# Microcontroller.net
KiCad netlist of a schematic drawn in Altium Designer
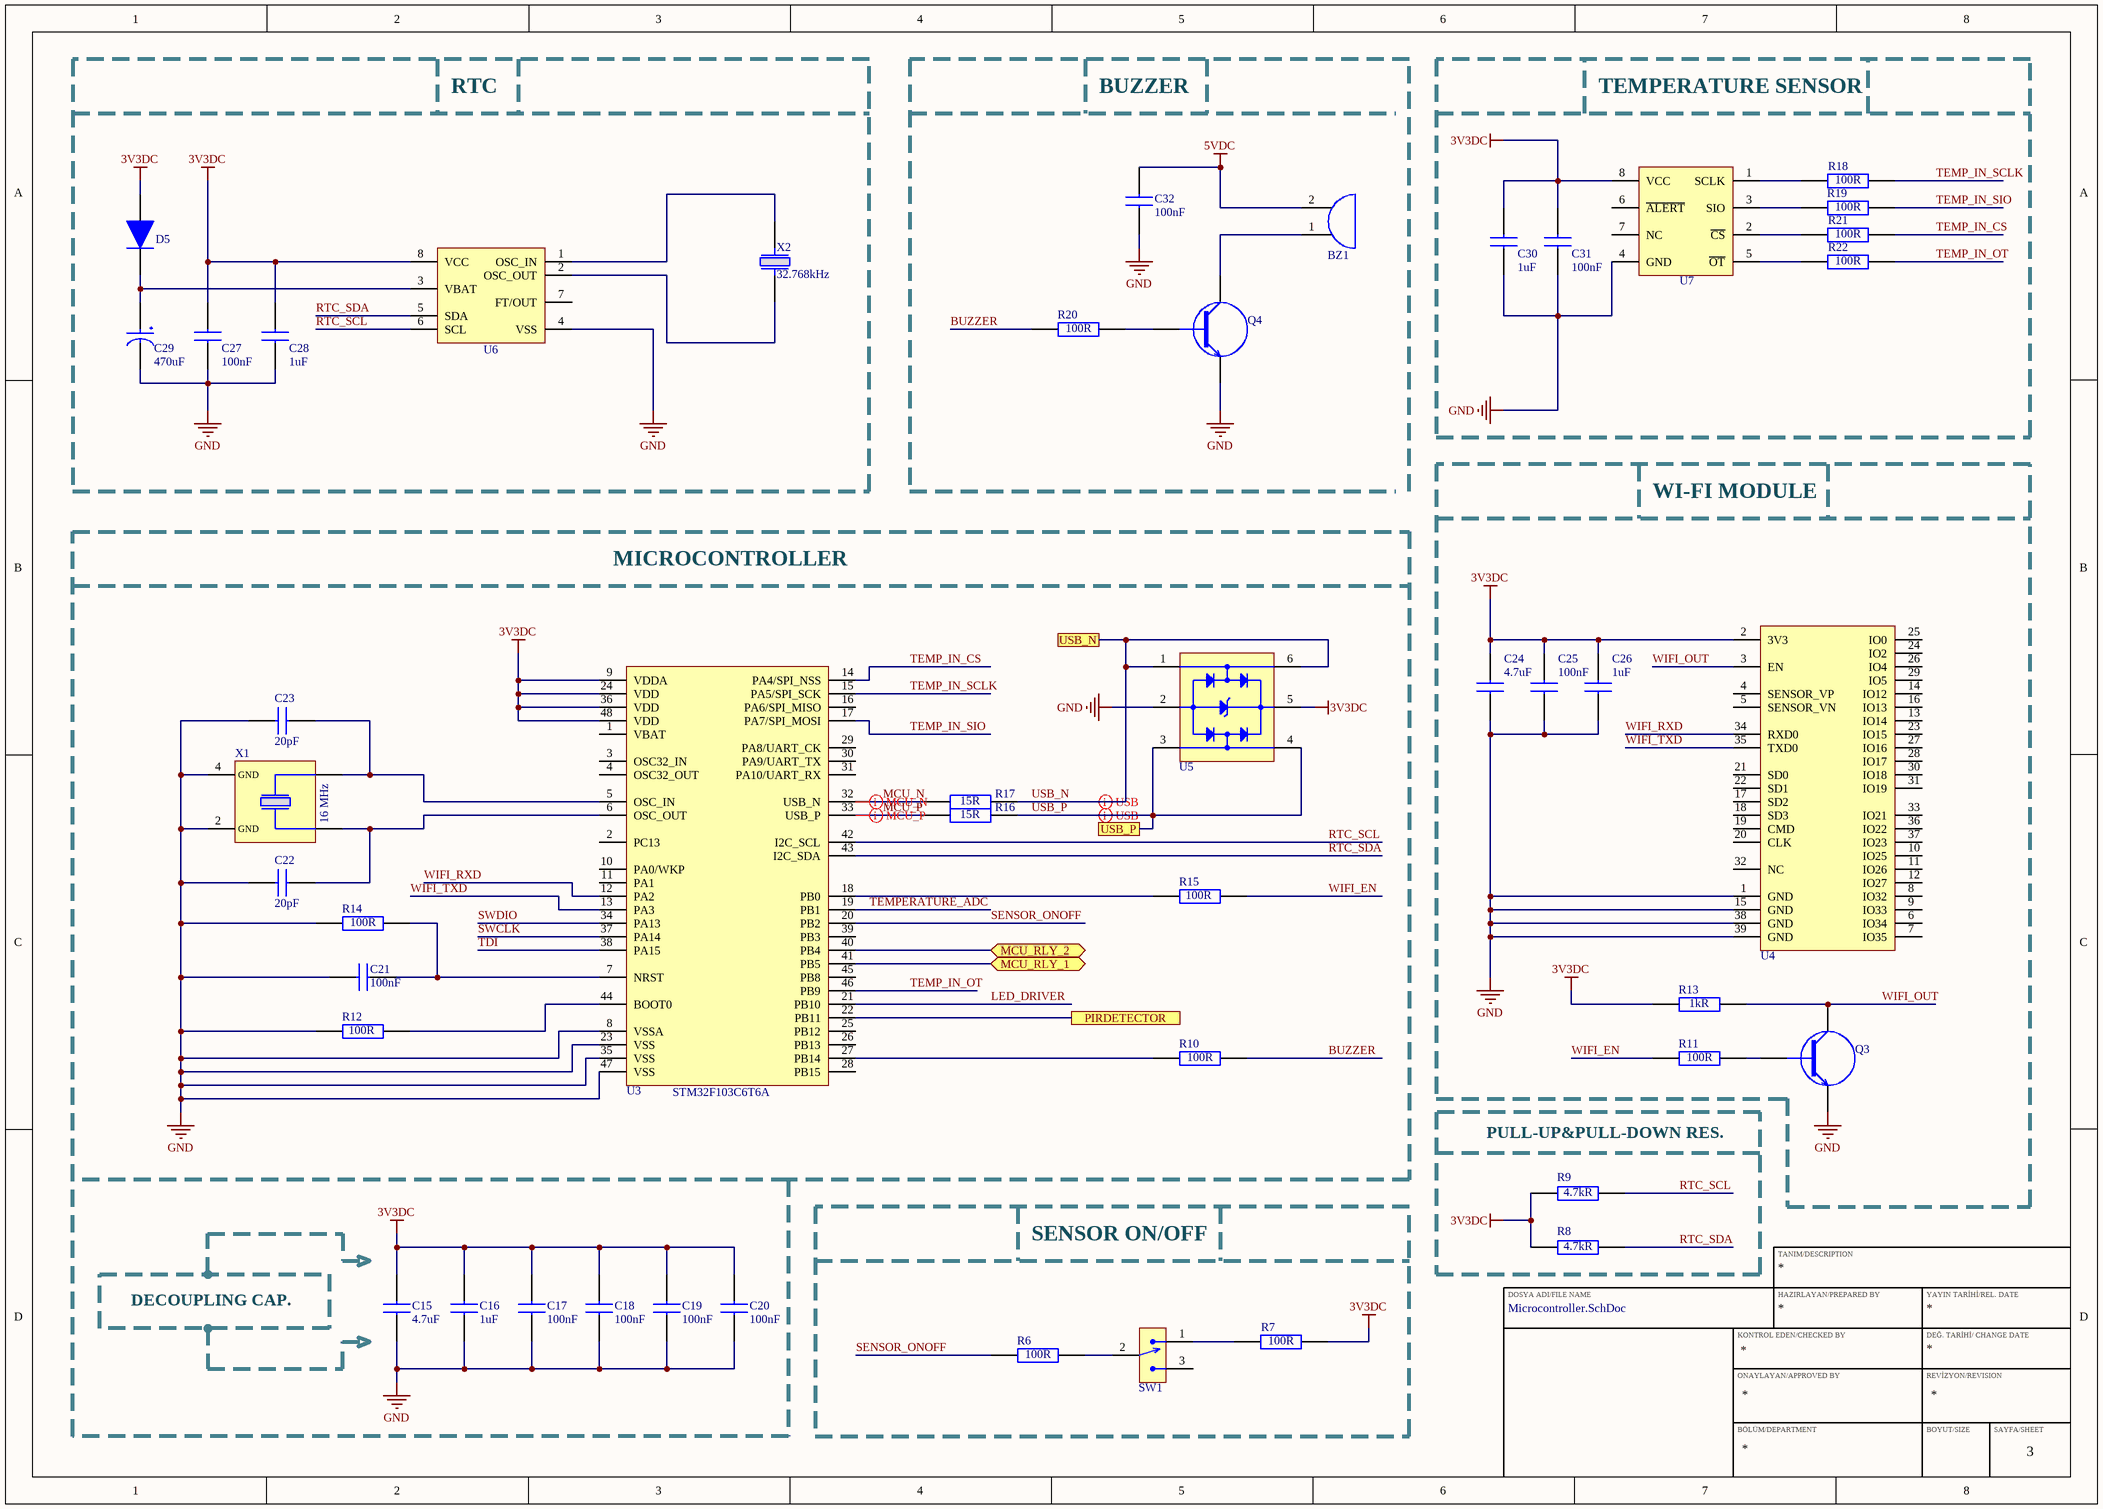
[diagram p0: Microcontroller.SchDoc]

(export (version "E")
  (design (tool "Eeschema 10.0.6"))
  (components
    (comp (ref "BZ1")
      (value "CMI-9605-0580T")
      (footprint "CMI-9605")
      (fields (field (name "MANUFACTURER") "CUI Devices") (field (name "DESIGNED BY") "ADAK"))
      (libsource (lib "Udemy_ADAK_Library1") (part "CMI-9605-0580T"))
    )
    (comp (ref "C15")
      (value "CL21A475KAQNNNE")
      (footprint "CAP_0805")
      (description "¦CAP CER 4.7UF %10 0805 SMD X5R")
      (fields
        (field (name "MANUFACTURER") "Samsung")
        (field (name "TOLERANCE") "10%")
        (field (name "CAPACITANCE") "4.7uF")
        (field (name "DESIGNED BY") "ADAK")
      )
      (libsource (lib "Udemy_ADAK_Library1") (part "CAP CER 4.7uF 0805"))
    )
    (comp (ref "C16")
      (value "CL21B105KBFNNNE")
      (footprint "CAP_0805")
      (description "¦CAP CER 1UF %10 0805 SMD X7R")
      (fields
        (field (name "MANUFACTURER") "Samsung")
        (field (name "TOLERANCE") "10%")
        (field (name "CAPACITANCE") "1uF")
        (field (name "DESIGNED BY") "ADAK")
      )
      (libsource (lib "Udemy_ADAK_Library1") (part "CAP CER 1uF 0805"))
    )
    (comp (ref "C17")
      (value "C0603C104K4RAC7867")
      (footprint "CAP_0603")
      (description "¦CAP CER 100nF (0.1UF) %10 0603 SMD")
      (fields
        (field (name "MANUFACTURER") "KEMET")
        (field (name "MANUFACTURER PART NUMBER") "C0603C104K4RACTU")
        (field (name "CAPACITANCE") "100nF")
        (field (name "DESIGNED BY") "ADAK")
      )
      (libsource (lib "Udemy_ADAK_Library1") (part "CAP CER 100nF 0603"))
    )
    (comp (ref "C18")
      (value "C0603C104K4RAC7867")
      (footprint "CAP_0603")
      (description "¦CAP CER 100nF (0.1UF) %10 0603 SMD")
      (fields
        (field (name "MANUFACTURER") "KEMET")
        (field (name "MANUFACTURER PART NUMBER") "C0603C104K4RACTU")
        (field (name "CAPACITANCE") "100nF")
        (field (name "DESIGNED BY") "ADAK")
      )
      (libsource (lib "Udemy_ADAK_Library1") (part "CAP CER 100nF 0603"))
    )
    (comp (ref "C19")
      (value "C0603C104K4RAC7867")
      (footprint "CAP_0603")
      (description "¦CAP CER 100nF (0.1UF) %10 0603 SMD")
      (fields
        (field (name "MANUFACTURER") "KEMET")
        (field (name "MANUFACTURER PART NUMBER") "C0603C104K4RACTU")
        (field (name "CAPACITANCE") "100nF")
        (field (name "DESIGNED BY") "ADAK")
      )
      (libsource (lib "Udemy_ADAK_Library1") (part "CAP CER 100nF 0603"))
    )
    (comp (ref "C20")
      (value "C0603C104K4RAC7867")
      (footprint "CAP_0603")
      (description "¦CAP CER 100nF (0.1UF) %10 0603 SMD")
      (fields
        (field (name "MANUFACTURER") "KEMET")
        (field (name "MANUFACTURER PART NUMBER") "C0603C104K4RACTU")
        (field (name "CAPACITANCE") "100nF")
        (field (name "DESIGNED BY") "ADAK")
      )
      (libsource (lib "Udemy_ADAK_Library1") (part "CAP CER 100nF 0603"))
    )
    (comp (ref "C21")
      (value "C0603C104K4RAC7867")
      (footprint "CAP_0603")
      (description "¦CAP CER 100nF (0.1UF) %10 0603 SMD")
      (fields
        (field (name "MANUFACTURER") "KEMET")
        (field (name "MANUFACTURER PART NUMBER") "C0603C104K4RACTU")
        (field (name "CAPACITANCE") "100nF")
        (field (name "DESIGNED BY") "ADAK")
      )
      (libsource (lib "Udemy_ADAK_Library1") (part "CAP CER 100nF 0603"))
    )
    (comp (ref "C22")
      (value "CL10C200JB8NNNC")
      (footprint "CAP_0603")
      (description "¦CAP CER 20pF %5 0603 SMD 50V")
      (fields
        (field (name "MANUFACTURER") "Samsung")
        (field (name "TOLERANCE") "5%")
        (field (name "CAPACITANCE") "20pF")
        (field (name "DESIGNED BY") "ADAK")
      )
      (libsource (lib "Udemy_ADAK_Library1") (part "CAP CER 20pF 0603"))
    )
    (comp (ref "C23")
      (value "CL10C200JB8NNNC")
      (footprint "CAP_0603")
      (description "¦CAP CER 20pF %5 0603 SMD 50V")
      (fields
        (field (name "MANUFACTURER") "Samsung")
        (field (name "TOLERANCE") "5%")
        (field (name "CAPACITANCE") "20pF")
        (field (name "DESIGNED BY") "ADAK")
      )
      (libsource (lib "Udemy_ADAK_Library1") (part "CAP CER 20pF 0603"))
    )
    (comp (ref "C24")
      (value "CL21A475KAQNNNE")
      (footprint "CAP_0805")
      (description "¦CAP CER 4.7UF %10 0805 SMD X5R")
      (fields
        (field (name "MANUFACTURER") "Samsung")
        (field (name "TOLERANCE") "10%")
        (field (name "CAPACITANCE") "4.7uF")
        (field (name "DESIGNED BY") "ADAK")
      )
      (libsource (lib "Udemy_ADAK_Library1") (part "CAP CER 4.7uF 0805"))
    )
    (comp (ref "C25")
      (value "CL21B104KBCNNNC")
      (footprint "CAP_0805")
      (description "¦CAP CER 0.1UF (100nF) %10 0805 SMD X7R")
      (fields
        (field (name "MANUFACTURER") "Samsung")
        (field (name "TOLERANCE") "10%")
        (field (name "CAPACITANCE") "100nF")
        (field (name "DESIGNED BY") "ADAK")
      )
      (libsource (lib "Udemy_ADAK_Library1") (part "CAP CER 100nF 0805"))
    )
    (comp (ref "C26")
      (value "CL21B105KBFNNNE")
      (footprint "CAP_0805")
      (description "¦CAP CER 1UF %10 0805 SMD X7R")
      (fields
        (field (name "MANUFACTURER") "Samsung")
        (field (name "TOLERANCE") "10%")
        (field (name "CAPACITANCE") "1uF")
        (field (name "DESIGNED BY") "ADAK")
      )
      (libsource (lib "Udemy_ADAK_Library1") (part "CAP CER 1uF 0805"))
    )
    (comp (ref "C27")
      (value "CL21B104KBCNNNC")
      (footprint "CAP_0805")
      (description "¦CAP CER 0.1UF (100nF) %10 0805 SMD X7R")
      (fields
        (field (name "MANUFACTURER") "Samsung")
        (field (name "TOLERANCE") "10%")
        (field (name "CAPACITANCE") "100nF")
        (field (name "DESIGNED BY") "ADAK")
      )
      (libsource (lib "Udemy_ADAK_Library1") (part "CAP CER 100nF 0805"))
    )
    (comp (ref "C28")
      (value "CL21B105KBFNNNE")
      (footprint "CAP_0805")
      (description "¦CAP CER 1UF %10 0805 SMD X7R")
      (fields
        (field (name "MANUFACTURER") "Samsung")
        (field (name "TOLERANCE") "10%")
        (field (name "CAPACITANCE") "1uF")
        (field (name "DESIGNED BY") "ADAK")
      )
      (libsource (lib "Udemy_ADAK_Library1") (part "CAP CER 1uF 0805"))
    )
    (comp (ref "C29")
      (value "ESH477M050AH4AA")
      (footprint "CAP_RADIAL_D10_P5")
      (description "¦CAP (AL) 470UF 20% 50V RADIAL")
      (fields
        (field (name "MANUFACTURER") "KEMET")
        (field (name "TOLERANCE") "20%")
        (field (name "CAPACITANCE") "470uF")
        (field (name "DESIGNED BY") "ADAK")
      )
      (libsource (lib "Udemy_ADAK_Library1") (part "CAP ALU ELEC 470uF 50V"))
    )
    (comp (ref "C30")
      (value "CL21B105KBFNNNE")
      (footprint "CAP_0805")
      (description "¦CAP CER 1UF %10 0805 SMD X7R")
      (fields
        (field (name "MANUFACTURER") "Samsung")
        (field (name "TOLERANCE") "10%")
        (field (name "CAPACITANCE") "1uF")
        (field (name "DESIGNED BY") "ADAK")
      )
      (libsource (lib "Udemy_ADAK_Library1") (part "CAP CER 1uF 0805"))
    )
    (comp (ref "C31")
      (value "CL21B104KBCNNNC")
      (footprint "CAP_0805")
      (description "¦CAP CER 0.1UF (100nF) %10 0805 SMD X7R")
      (fields
        (field (name "MANUFACTURER") "Samsung")
        (field (name "TOLERANCE") "10%")
        (field (name "CAPACITANCE") "100nF")
        (field (name "DESIGNED BY") "ADAK")
      )
      (libsource (lib "Udemy_ADAK_Library1") (part "CAP CER 100nF 0805"))
    )
    (comp (ref "C32")
      (value "CL21B104KBCNNNC")
      (footprint "CAP_0805")
      (description "¦CAP CER 0.1UF (100nF) %10 0805 SMD X7R")
      (fields
        (field (name "MANUFACTURER") "Samsung")
        (field (name "TOLERANCE") "10%")
        (field (name "CAPACITANCE") "100nF")
        (field (name "DESIGNED BY") "ADAK")
      )
      (libsource (lib "Udemy_ADAK_Library1") (part "CAP CER 100nF 0805"))
    )
    (comp (ref "D5")
      (value "1N4148WS")
      (footprint "SOD323F")
      (description "¦Diode 75 V 150mA Surface Mount SOD-323F")
      (fields
        (field (name "MANUFACTURER") "ON Semiconductor / Fairchild")
        (field (name "DESIGNED BY") "ADAK")
      )
      (libsource (lib "Udemy_ADAK_Library1") (part "1N4148WS"))
    )
    (comp (ref "Q3")
      (value "MMBT3904-7-F")
      (footprint "SOT-23F")
      (description "¦Bipolar (BJT) Transistor NPN 40 V 200 mA 300MHz 300 mW Surface Mount SOT-23-3")
      (fields (field (name "MANUFACTURER") "Diodes Zetex") (field (name "DESIGNED BY") "ADAK"))
      (libsource (lib "Udemy_ADAK_Library1") (part "MMBT3904-7-F"))
    )
    (comp (ref "Q4")
      (value "MMBT3904-7-F")
      (footprint "SOT-23F")
      (description "¦Bipolar (BJT) Transistor NPN 40 V 200 mA 300MHz 300 mW Surface Mount SOT-23-3")
      (fields (field (name "MANUFACTURER") "Diodes Zetex") (field (name "DESIGNED BY") "ADAK"))
      (libsource (lib "Udemy_ADAK_Library1") (part "MMBT3904-7-F"))
    )
    (comp (ref "R6")
      (value "RC0603JR-13100RL")
      (footprint "RES_0603")
      (description "¦RES 100Ω 5% 0603 SMD")
      (fields
        (field (name "MANUFACTURER") "Yageo")
        (field (name "TOLERANCE") "5%")
        (field (name "RESISTANCE") "100R")
        (field (name "DESIGNED BY") "ADAK")
      )
      (libsource (lib "Udemy_ADAK_Library1") (part "RES 100 OHM 0603"))
    )
    (comp (ref "R7")
      (value "RC0603JR-13100RL")
      (footprint "RES_0603")
      (description "¦RES 100Ω 5% 0603 SMD")
      (fields
        (field (name "MANUFACTURER") "Yageo")
        (field (name "TOLERANCE") "5%")
        (field (name "RESISTANCE") "100R")
        (field (name "DESIGNED BY") "ADAK")
      )
      (libsource (lib "Udemy_ADAK_Library1") (part "RES 100 OHM 0603"))
    )
    (comp (ref "R8")
      (value "RC0603JR-074K7L")
      (footprint "RES_0603")
      (description "¦RES 4K7Ω 5% 0603 SMD")
      (fields
        (field (name "MANUFACTURER") "Yageo")
        (field (name "TOLERANCE") "5%")
        (field (name "RESISTANCE") "4.7kR")
        (field (name "DESIGNED BY") "ADAK")
      )
      (libsource (lib "Udemy_ADAK_Library1") (part "RES 4K7 OHM 0603"))
    )
    (comp (ref "R9")
      (value "RC0603JR-074K7L")
      (footprint "RES_0603")
      (description "¦RES 4K7Ω 5% 0603 SMD")
      (fields
        (field (name "MANUFACTURER") "Yageo")
        (field (name "TOLERANCE") "5%")
        (field (name "RESISTANCE") "4.7kR")
        (field (name "DESIGNED BY") "ADAK")
      )
      (libsource (lib "Udemy_ADAK_Library1") (part "RES 4K7 OHM 0603"))
    )
    (comp (ref "R10")
      (value "RC0603JR-13100RL")
      (footprint "RES_0603")
      (description "¦RES 100Ω 5% 0603 SMD")
      (fields
        (field (name "MANUFACTURER") "Yageo")
        (field (name "TOLERANCE") "5%")
        (field (name "RESISTANCE") "100R")
        (field (name "DESIGNED BY") "ADAK")
      )
      (libsource (lib "Udemy_ADAK_Library1") (part "RES 100 OHM 0603"))
    )
    (comp (ref "R11")
      (value "RC0603JR-13100RL")
      (footprint "RES_0603")
      (description "¦RES 100Ω 5% 0603 SMD")
      (fields
        (field (name "MANUFACTURER") "Yageo")
        (field (name "TOLERANCE") "5%")
        (field (name "RESISTANCE") "100R")
        (field (name "DESIGNED BY") "ADAK")
      )
      (libsource (lib "Udemy_ADAK_Library1") (part "RES 100 OHM 0603"))
    )
    (comp (ref "R12")
      (value "RC0603JR-13100RL")
      (footprint "RES_0603")
      (description "¦RES 100Ω 5% 0603 SMD")
      (fields
        (field (name "MANUFACTURER") "Yageo")
        (field (name "TOLERANCE") "5%")
        (field (name "RESISTANCE") "100R")
        (field (name "DESIGNED BY") "ADAK")
      )
      (libsource (lib "Udemy_ADAK_Library1") (part "RES 100 OHM 0603"))
    )
    (comp (ref "R13")
      (value "RC0603FR-071KL")
      (footprint "RES_0603")
      (description "¦RES 1KΩ 1% 0603 SMD")
      (fields
        (field (name "MANUFACTURER") "Yageo")
        (field (name "TOLERANCE") "1%")
        (field (name "RESISTANCE") "1kR")
        (field (name "DESIGNED BY") "ADAK")
      )
      (libsource (lib "Udemy_ADAK_Library1") (part "RES 1K OHM 0603"))
    )
    (comp (ref "R14")
      (value "RC0603JR-13100RL")
      (footprint "RES_0603")
      (description "¦RES 100Ω 5% 0603 SMD")
      (fields
        (field (name "MANUFACTURER") "Yageo")
        (field (name "TOLERANCE") "5%")
        (field (name "RESISTANCE") "100R")
        (field (name "DESIGNED BY") "ADAK")
      )
      (libsource (lib "Udemy_ADAK_Library1") (part "RES 100 OHM 0603"))
    )
    (comp (ref "R15")
      (value "RC0603JR-13100RL")
      (footprint "RES_0603")
      (description "¦RES 100Ω 5% 0603 SMD")
      (fields
        (field (name "MANUFACTURER") "Yageo")
        (field (name "TOLERANCE") "5%")
        (field (name "RESISTANCE") "100R")
        (field (name "DESIGNED BY") "ADAK")
      )
      (libsource (lib "Udemy_ADAK_Library1") (part "RES 100 OHM 0603"))
    )
    (comp (ref "R16")
      (value "RC0603JR-0715RL")
      (footprint "RES_0603")
      (description "¦RES 15Ω 1% 0603 SMD")
      (fields
        (field (name "MANUFACTURER") "Yageo")
        (field (name "TOLERANCE") "5%")
        (field (name "RESISTANCE") "15R")
        (field (name "DESIGNED BY") "ADAK")
      )
      (libsource (lib "Udemy_ADAK_Library1") (part "RES 15 OHM 0603"))
    )
    (comp (ref "R17")
      (value "RC0603JR-0715RL")
      (footprint "RES_0603")
      (description "¦RES 15Ω 1% 0603 SMD")
      (fields
        (field (name "MANUFACTURER") "Yageo")
        (field (name "TOLERANCE") "5%")
        (field (name "RESISTANCE") "15R")
        (field (name "DESIGNED BY") "ADAK")
      )
      (libsource (lib "Udemy_ADAK_Library1") (part "RES 15 OHM 0603"))
    )
    (comp (ref "R18")
      (value "RC0603JR-13100RL")
      (footprint "RES_0603")
      (description "¦RES 100Ω 5% 0603 SMD")
      (fields
        (field (name "MANUFACTURER") "Yageo")
        (field (name "TOLERANCE") "5%")
        (field (name "RESISTANCE") "100R")
        (field (name "DESIGNED BY") "ADAK")
      )
      (libsource (lib "Udemy_ADAK_Library1") (part "RES 100 OHM 0603"))
    )
    (comp (ref "R19")
      (value "RC0603JR-13100RL")
      (footprint "RES_0603")
      (description "¦RES 100Ω 5% 0603 SMD")
      (fields
        (field (name "MANUFACTURER") "Yageo")
        (field (name "TOLERANCE") "5%")
        (field (name "RESISTANCE") "100R")
        (field (name "DESIGNED BY") "ADAK")
      )
      (libsource (lib "Udemy_ADAK_Library1") (part "RES 100 OHM 0603"))
    )
    (comp (ref "R20")
      (value "RC0603JR-13100RL")
      (footprint "RES_0603")
      (description "¦RES 100Ω 5% 0603 SMD")
      (fields
        (field (name "MANUFACTURER") "Yageo")
        (field (name "TOLERANCE") "5%")
        (field (name "RESISTANCE") "100R")
        (field (name "DESIGNED BY") "ADAK")
      )
      (libsource (lib "Udemy_ADAK_Library1") (part "RES 100 OHM 0603"))
    )
    (comp (ref "R21")
      (value "RC0603JR-13100RL")
      (footprint "RES_0603")
      (description "¦RES 100Ω 5% 0603 SMD")
      (fields
        (field (name "MANUFACTURER") "Yageo")
        (field (name "TOLERANCE") "5%")
        (field (name "RESISTANCE") "100R")
        (field (name "DESIGNED BY") "ADAK")
      )
      (libsource (lib "Udemy_ADAK_Library1") (part "RES 100 OHM 0603"))
    )
    (comp (ref "R22")
      (value "RC0603JR-13100RL")
      (footprint "RES_0603")
      (description "¦RES 100Ω 5% 0603 SMD")
      (fields
        (field (name "MANUFACTURER") "Yageo")
        (field (name "TOLERANCE") "5%")
        (field (name "RESISTANCE") "100R")
        (field (name "DESIGNED BY") "ADAK")
      )
      (libsource (lib "Udemy_ADAK_Library1") (part "RES 100 OHM 0603"))
    )
    (comp (ref "SW1")
      (value "EG1215AA")
      (footprint "EG1215AA")
      (description "¦Slide Switch SPDT Surface Mount, Right Angle")
      (fields
        (field (name "MANUFACTURER") "E-Switch")
        (field (name "TOLERANCE") "4.95%")
        (field (name "DESIGNED BY") "ADAK")
      )
      (libsource (lib "Udemy_ADAK_Library1") (part "EG1215AA"))
    )
    (comp (ref "U3")
      (value "STM32F103C6T6A")
      (footprint "LQFP-48")
      (description "¦MCU 32-bit STM32F ARM Cortex M3 RISC 32KB Flash 2.5V/3.3V 48-Pin LQFP Tray")
      (fields (field (name "MANUFACTURER") "STMicroelectronics") (field (name "DESIGNED BY") "ADAK"))
      (libsource (lib "Udemy_ADAK_Library1") (part "STM32F103C6T6A"))
    )
    (comp (ref "U4")
      (value "ESP32-WROOM-32E-N4")
      (footprint "ESP32-32E-N4")
      (fields
        (field (name "MANUFACTURER") "Espressif Systems")
        (field (name "MANUFACTURER PART NUMBER") "ESP32-WROOM-32E(M113EH3200PH3Q0)")
        (field (name "DESIGNED BY") "ADAK")
      )
      (libsource (lib "Udemy_ADAK_Library1") (part "ESP32-WROOM"))
    )
    (comp (ref "U5")
      (value "USBLC6-2SC6")
      (footprint "SOT23-6L")
      (description "¦17V Clamp 5A (8/20µs) Ipp Tvs Diode Surface Mount SOT-23-6")
      (fields (field (name "MANUFACTURER") "STMicroelectronics") (field (name "DESIGNED BY") "ADAK"))
      (libsource (lib "Udemy_ADAK_Library1") (part "USB PROTECTION"))
    )
    (comp (ref "U6")
      (value "M41T0M6F")
      (footprint "SOIC8")
      (description "¦RTC M41T0 Series 2 to 5.5 V Serial I2C Real Time Clock Surface Mount - SOIC-8")
      (fields (field (name "MANUFACTURER") "STMicroelectronics") (field (name "DESIGNED BY") "ADAK"))
      (libsource (lib "Udemy_ADAK_Library1") (part "M41T0M6F"))
    )
    (comp (ref "U7")
      (value "MAX6662MSA+")
      (footprint "SOIC8")
      (description "¦Temperature Sensor Digital, 8-SOIC, SPI")
      (fields (field (name "MANUFACTURER") "Maxim") (field (name "DESIGNED BY") "ADAK"))
      (libsource (lib "Udemy_ADAK_Library1") (part "MAX6662MSA+"))
    )
    (comp (ref "X1")
      (value "ECS-160-20-30B-TR")
      (footprint "ECS")
      (description "¦16 MHz ±30ppm Crystal 20pF 50 Ohms 4-SMD, No Lead")
      (fields
        (field (name "MANUFACTURER") "ECS International")
        (field (name "TOLERANCE") "50ppm")
        (field (name "FREQUENCY") "16 MHz")
        (field (name "DESIGNED BY") "ADAK")
      )
      (libsource (lib "Udemy_ADAK_Library1") (part "CRYSTAL 16MHZ"))
    )
    (comp (ref "X2")
      (value "ABS05-32.768KHZ-T")
      (footprint "ABS05")
      (description "¦32.768 kHz ±20ppm Crystal 12.5pF 90 kOhms 2-SMD, No Lead")
      (fields
        (field (name "MANUFACTURER") "Abracon")
        (field (name "TOLERANCE") "20ppm")
        (field (name "FREQUENCY") "32.768kHz")
        (field (name "DESIGNED BY") "ADAK")
      )
      (libsource (lib "Udemy_ADAK_Library1") (part "CRYSTAL 32.768kHZ"))
    )
  )
  (nets
    (net (code "1") (name "/BUZZER") (class "Default")
      (node (ref "R10") (pin "2") (pinfunction "2_2") (pintype "passive"))
      (node (ref "R20") (pin "1") (pinfunction "1_1") (pintype "passive"))
    )
    (net (code "2") (name "/LED_DRIVER") (class "Default")
      (node (ref "U3") (pin "21") (pinfunction "PB10_21") (pintype "passive"))
    )
    (net (code "3") (name "/MCU_N") (class "Default")
      (node (ref "R17") (pin "1") (pinfunction "1_1") (pintype "passive"))
      (node (ref "U3") (pin "32") (pinfunction "USB_N_32") (pintype "passive"))
    )
    (net (code "4") (name "/MCU_P") (class "Default")
      (node (ref "R16") (pin "1") (pinfunction "1_1") (pintype "passive"))
      (node (ref "U3") (pin "33") (pinfunction "USB_P_33") (pintype "passive"))
    )
    (net (code "5") (name "/MCU_RLY_1") (class "Default")
      (node (ref "U3") (pin "41") (pinfunction "PB5_41") (pintype "passive"))
    )
    (net (code "6") (name "/MCU_RLY_2") (class "Default")
      (node (ref "U3") (pin "40") (pinfunction "PB4_40") (pintype "passive"))
    )
    (net (code "7") (name "/PIRDETECTOR") (class "Default")
      (node (ref "U3") (pin "22") (pinfunction "PB11_22") (pintype "passive"))
    )
    (net (code "8") (name "/RTC_SCL") (class "Default")
      (node (ref "R9") (pin "1") (pinfunction "1_1") (pintype "passive"))
      (node (ref "U3") (pin "42") (pinfunction "I2C_SCL_42") (pintype "passive"))
      (node (ref "U6") (pin "6") (pinfunction "SCL_6") (pintype "passive"))
    )
    (net (code "9") (name "/RTC_SDA") (class "Default")
      (node (ref "R8") (pin "1") (pinfunction "1_1") (pintype "passive"))
      (node (ref "U3") (pin "43") (pinfunction "I2C_SDA_43") (pintype "passive"))
      (node (ref "U6") (pin "5") (pinfunction "SDA_5") (pintype "passive"))
    )
    (net (code "10") (name "/SENSOR_ONOFF") (class "Default")
      (node (ref "R6") (pin "1") (pinfunction "1_1") (pintype "passive"))
      (node (ref "U3") (pin "20") (pinfunction "PB2_20") (pintype "passive"))
    )
    (net (code "11") (name "/SWCLK") (class "Default")
      (node (ref "U3") (pin "37") (pinfunction "PA14_37") (pintype "passive"))
    )
    (net (code "12") (name "/SWDIO") (class "Default")
      (node (ref "U3") (pin "34") (pinfunction "PA13_34") (pintype "passive"))
    )
    (net (code "13") (name "/TDI") (class "Default")
      (node (ref "U3") (pin "38") (pinfunction "PA15_38") (pintype "passive"))
    )
    (net (code "14") (name "/TEMPERATURE_ADC") (class "Default")
      (node (ref "U3") (pin "19") (pinfunction "PB1_19") (pintype "passive"))
    )
    (net (code "15") (name "/TEMP_IN_CS") (class "Default")
      (node (ref "R21") (pin "1") (pinfunction "1_1") (pintype "passive"))
      (node (ref "U3") (pin "14") (pinfunction "PA4/SPI_NSS_14") (pintype "passive"))
    )
    (net (code "16") (name "/TEMP_IN_OT") (class "Default")
      (node (ref "R22") (pin "1") (pinfunction "1_1") (pintype "passive"))
      (node (ref "U3") (pin "46") (pinfunction "PB9_46") (pintype "passive"))
    )
    (net (code "17") (name "/TEMP_IN_SCLK") (class "Default")
      (node (ref "R18") (pin "1") (pinfunction "1_1") (pintype "passive"))
      (node (ref "U3") (pin "15") (pinfunction "PA5/SPI_SCK_15") (pintype "passive"))
    )
    (net (code "18") (name "/TEMP_IN_SIO") (class "Default")
      (node (ref "R19") (pin "1") (pinfunction "1_1") (pintype "passive"))
      (node (ref "U3") (pin "17") (pinfunction "PA7/SPI_MOSI_17") (pintype "passive"))
    )
    (net (code "19") (name "/USB_N") (class "Default")
      (node (ref "R17") (pin "2") (pinfunction "2_2") (pintype "passive"))
      (node (ref "U5") (pin "1") (pinfunction "I/O1_1") (pintype "passive"))
      (node (ref "U5") (pin "6") (pinfunction "I/O1_6") (pintype "passive"))
    )
    (net (code "20") (name "/USB_P") (class "Default")
      (node (ref "R16") (pin "2") (pinfunction "2_2") (pintype "passive"))
      (node (ref "U5") (pin "3") (pinfunction "I/O2_3") (pintype "passive"))
      (node (ref "U5") (pin "4") (pinfunction "I/O2_4") (pintype "passive"))
    )
    (net (code "21") (name "/WIFI_EN") (class "Default")
      (node (ref "R11") (pin "1") (pinfunction "1_1") (pintype "passive"))
      (node (ref "R15") (pin "2") (pinfunction "2_2") (pintype "passive"))
    )
    (net (code "22") (name "/WIFI_OUT") (class "Default")
      (node (ref "Q3") (pin "3") (pinfunction "C_3") (pintype "passive"))
      (node (ref "R13") (pin "2") (pinfunction "2_2") (pintype "passive"))
      (node (ref "U4") (pin "3") (pinfunction "EN_3") (pintype "passive"))
    )
    (net (code "23") (name "/WIFI_RXD") (class "Default")
      (node (ref "U3") (pin "12") (pinfunction "PA2_12") (pintype "passive"))
      (node (ref "U4") (pin "34") (pinfunction "RXD0_34") (pintype "passive"))
    )
    (net (code "24") (name "/WIFI_TXD") (class "Default")
      (node (ref "U3") (pin "13") (pinfunction "PA3_13") (pintype "passive"))
      (node (ref "U4") (pin "35") (pinfunction "TXD0_35") (pintype "passive"))
    )
    (net (code "25") (name "3V3DC") (class "Default")
      (node (ref "C15") (pin "2") (pinfunction "2_2") (pintype "passive"))
      (node (ref "C16") (pin "2") (pinfunction "2_2") (pintype "passive"))
      (node (ref "C17") (pin "2") (pinfunction "2_2") (pintype "passive"))
      (node (ref "C18") (pin "2") (pinfunction "2_2") (pintype "passive"))
      (node (ref "C19") (pin "2") (pinfunction "2_2") (pintype "passive"))
      (node (ref "C20") (pin "2") (pinfunction "2_2") (pintype "passive"))
      (node (ref "C24") (pin "2") (pinfunction "2_2") (pintype "passive"))
      (node (ref "C25") (pin "2") (pinfunction "2_2") (pintype "passive"))
      (node (ref "C26") (pin "2") (pinfunction "2_2") (pintype "passive"))
      (node (ref "C27") (pin "2") (pinfunction "2_2") (pintype "passive"))
      (node (ref "C28") (pin "2") (pinfunction "2_2") (pintype "passive"))
      (node (ref "C30") (pin "2") (pinfunction "2_2") (pintype "passive"))
      (node (ref "C31") (pin "2") (pinfunction "2_2") (pintype "passive"))
      (node (ref "D5") (pin "2") (pinfunction "2_2") (pintype "passive"))
      (node (ref "R13") (pin "1") (pinfunction "1_1") (pintype "passive"))
      (node (ref "R7") (pin "2") (pinfunction "2_2") (pintype "passive"))
      (node (ref "R8") (pin "2") (pinfunction "2_2") (pintype "passive"))
      (node (ref "R9") (pin "2") (pinfunction "2_2") (pintype "passive"))
      (node (ref "U3") (pin "24") (pinfunction "VDD_24") (pintype "passive"))
      (node (ref "U3") (pin "36") (pinfunction "VDD_36") (pintype "passive"))
      (node (ref "U3") (pin "48") (pinfunction "VDD_48") (pintype "passive"))
      (node (ref "U3") (pin "9") (pinfunction "VDDA_9") (pintype "passive"))
      (node (ref "U4") (pin "2") (pinfunction "3V3_2") (pintype "passive"))
      (node (ref "U5") (pin "5") (pinfunction "VBUS_5") (pintype "passive"))
      (node (ref "U6") (pin "8") (pinfunction "VCC_8") (pintype "passive"))
      (node (ref "U7") (pin "8") (pinfunction "VCC_8") (pintype "passive"))
    )
    (net (code "26") (name "5VDC") (class "Default")
      (node (ref "BZ1") (pin "2") (pinfunction "2_2") (pintype "passive"))
      (node (ref "C32") (pin "2") (pinfunction "2_2") (pintype "passive"))
    )
    (net (code "27") (name "GND") (class "Default")
      (node (ref "C15") (pin "1") (pinfunction "1_1") (pintype "passive"))
      (node (ref "C16") (pin "1") (pinfunction "1_1") (pintype "passive"))
      (node (ref "C17") (pin "1") (pinfunction "1_1") (pintype "passive"))
      (node (ref "C18") (pin "1") (pinfunction "1_1") (pintype "passive"))
      (node (ref "C19") (pin "1") (pinfunction "1_1") (pintype "passive"))
      (node (ref "C20") (pin "1") (pinfunction "1_1") (pintype "passive"))
      (node (ref "C21") (pin "1") (pinfunction "1_1") (pintype "passive"))
      (node (ref "C22") (pin "1") (pinfunction "1_1") (pintype "passive"))
      (node (ref "C23") (pin "1") (pinfunction "1_1") (pintype "passive"))
      (node (ref "C24") (pin "1") (pinfunction "1_1") (pintype "passive"))
      (node (ref "C25") (pin "1") (pinfunction "1_1") (pintype "passive"))
      (node (ref "C26") (pin "1") (pinfunction "1_1") (pintype "passive"))
      (node (ref "C27") (pin "1") (pinfunction "1_1") (pintype "passive"))
      (node (ref "C28") (pin "1") (pinfunction "1_1") (pintype "passive"))
      (node (ref "C29") (pin "2") (pinfunction "2_2") (pintype "passive"))
      (node (ref "C30") (pin "1") (pinfunction "1_1") (pintype "passive"))
      (node (ref "C31") (pin "1") (pinfunction "1_1") (pintype "passive"))
      (node (ref "C32") (pin "1") (pinfunction "1_1") (pintype "passive"))
      (node (ref "Q3") (pin "2") (pinfunction "E_2") (pintype "passive"))
      (node (ref "Q4") (pin "2") (pinfunction "E_2") (pintype "passive"))
      (node (ref "R12") (pin "1") (pinfunction "1_1") (pintype "passive"))
      (node (ref "R14") (pin "1") (pinfunction "1_1") (pintype "passive"))
      (node (ref "U3") (pin "23") (pinfunction "VSS_23") (pintype "passive"))
      (node (ref "U3") (pin "35") (pinfunction "VSS_35") (pintype "passive"))
      (node (ref "U3") (pin "47") (pinfunction "VSS_47") (pintype "passive"))
      (node (ref "U3") (pin "8") (pinfunction "VSSA_8") (pintype "passive"))
      (node (ref "U4") (pin "1") (pinfunction "GND_1") (pintype "passive"))
      (node (ref "U4") (pin "15") (pinfunction "GND_15") (pintype "passive"))
      (node (ref "U4") (pin "38") (pinfunction "GND_38") (pintype "passive"))
      (node (ref "U4") (pin "39") (pinfunction "GND_39") (pintype "passive"))
      (node (ref "U5") (pin "2") (pinfunction "GND_2") (pintype "passive"))
      (node (ref "U6") (pin "4") (pinfunction "VSS_4") (pintype "passive"))
      (node (ref "U7") (pin "4") (pinfunction "GND_4") (pintype "passive"))
      (node (ref "X1") (pin "2") (pinfunction "GND_2") (pintype "passive"))
      (node (ref "X1") (pin "4") (pinfunction "GND_4") (pintype "passive"))
    )
    (net (code "28") (name "Net-(Q3-B)") (class "Default")
      (node (ref "Q3") (pin "1") (pinfunction "B_1") (pintype "passive"))
      (node (ref "R11") (pin "2") (pinfunction "2_2") (pintype "passive"))
    )
    (net (code "29") (name "Net-(Q4-B)") (class "Default")
      (node (ref "Q4") (pin "1") (pinfunction "B_1") (pintype "passive"))
      (node (ref "R20") (pin "2") (pinfunction "2_2") (pintype "passive"))
    )
    (net (code "30") (name "Net-(Q4-C)") (class "Default")
      (node (ref "BZ1") (pin "1") (pinfunction "1_1") (pintype "passive"))
      (node (ref "Q4") (pin "3") (pinfunction "C_3") (pintype "passive"))
    )
    (net (code "31") (name "Net-(R6-Pad2)") (class "Default")
      (node (ref "R6") (pin "2") (pinfunction "2_2") (pintype "passive"))
      (node (ref "SW1") (pin "2") (pinfunction "2_2") (pintype "passive"))
    )
    (net (code "32") (name "Net-(R7-Pad1)") (class "Default")
      (node (ref "R7") (pin "1") (pinfunction "1_1") (pintype "passive"))
      (node (ref "SW1") (pin "1") (pinfunction "1_1") (pintype "passive"))
    )
    (net (code "33") (name "Net-(U3-BOOT0)") (class "Default")
      (node (ref "R12") (pin "2") (pinfunction "2_2") (pintype "passive"))
      (node (ref "U3") (pin "44") (pinfunction "BOOT0_44") (pintype "passive"))
    )
    (net (code "34") (name "Net-(U3-NRST)") (class "Default")
      (node (ref "C21") (pin "2") (pinfunction "2_2") (pintype "passive"))
      (node (ref "R14") (pin "2") (pinfunction "2_2") (pintype "passive"))
      (node (ref "U3") (pin "7") (pinfunction "NRST_7") (pintype "passive"))
    )
    (net (code "35") (name "Net-(U3-OSC_IN)") (class "Default")
      (node (ref "C23") (pin "2") (pinfunction "2_2") (pintype "passive"))
      (node (ref "U3") (pin "5") (pinfunction "OSC_IN_5") (pintype "passive"))
      (node (ref "X1") (pin "3") (pinfunction "3_3") (pintype "passive"))
    )
    (net (code "36") (name "Net-(U3-OSC_OUT)") (class "Default")
      (node (ref "C22") (pin "2") (pinfunction "2_2") (pintype "passive"))
      (node (ref "U3") (pin "6") (pinfunction "OSC_OUT_6") (pintype "passive"))
      (node (ref "X1") (pin "1") (pinfunction "1_1") (pintype "passive"))
    )
    (net (code "37") (name "Net-(U3-PB0)") (class "Default")
      (node (ref "R15") (pin "1") (pinfunction "1_1") (pintype "passive"))
      (node (ref "U3") (pin "18") (pinfunction "PB0_18") (pintype "passive"))
    )
    (net (code "38") (name "Net-(U3-PB14)") (class "Default")
      (node (ref "R10") (pin "1") (pinfunction "1_1") (pintype "passive"))
      (node (ref "U3") (pin "27") (pinfunction "PB14_27") (pintype "passive"))
    )
    (net (code "39") (name "Net-(U6-OSC_IN)") (class "Default")
      (node (ref "U6") (pin "1") (pinfunction "OSC_IN_1") (pintype "passive"))
      (node (ref "X2") (pin "2") (pinfunction "2_2") (pintype "passive"))
    )
    (net (code "40") (name "Net-(U6-OSC_OUT)") (class "Default")
      (node (ref "U6") (pin "2") (pinfunction "OSC_OUT_2") (pintype "passive"))
      (node (ref "X2") (pin "1") (pinfunction "1_1") (pintype "passive"))
    )
    (net (code "41") (name "Net-(U6-VBAT)") (class "Default")
      (node (ref "C29") (pin "1") (pinfunction "1_1") (pintype "passive"))
      (node (ref "D5") (pin "1") (pinfunction "1_1") (pintype "passive"))
      (node (ref "U6") (pin "3") (pinfunction "VBAT_3") (pintype "passive"))
    )
    (net (code "42") (name "Net-(U7-SCLK)") (class "Default")
      (node (ref "R18") (pin "2") (pinfunction "2_2") (pintype "passive"))
      (node (ref "U7") (pin "1") (pinfunction "SCLK_1") (pintype "passive"))
    )
    (net (code "43") (name "Net-(U7-SIO)") (class "Default")
      (node (ref "R19") (pin "2") (pinfunction "2_2") (pintype "passive"))
      (node (ref "U7") (pin "3") (pinfunction "SIO_3") (pintype "passive"))
    )
    (net (code "44") (name "Net-(U7-~{CS})") (class "Default")
      (node (ref "R21") (pin "2") (pinfunction "2_2") (pintype "passive"))
      (node (ref "U7") (pin "2") (pinfunction "~{CS}_2") (pintype "passive"))
    )
    (net (code "45") (name "Net-(U7-~{OT})") (class "Default")
      (node (ref "R22") (pin "2") (pinfunction "2_2") (pintype "passive"))
      (node (ref "U7") (pin "5") (pinfunction "~{OT}_5") (pintype "passive"))
    )
    (net (code "46") (name "unconnected-(SW1-Pad3)") (class "Default")
      (node (ref "SW1") (pin "3") (pinfunction "3_3") (pintype "passive"))
    )
    (net (code "47") (name "unconnected-(U3-OSC32_IN-Pad3)") (class "Default")
      (node (ref "U3") (pin "3") (pinfunction "OSC32_IN_3") (pintype "passive"))
    )
    (net (code "48") (name "unconnected-(U3-OSC32_OUT-Pad4)") (class "Default")
      (node (ref "U3") (pin "4") (pinfunction "OSC32_OUT_4") (pintype "passive"))
    )
    (net (code "49") (name "unconnected-(U3-PA0{slash}WKP-Pad10)") (class "Default")
      (node (ref "U3") (pin "10") (pinfunction "PA0/WKP_10") (pintype "passive"))
    )
    (net (code "50") (name "unconnected-(U3-PA1-Pad11)") (class "Default")
      (node (ref "U3") (pin "11") (pinfunction "PA1_11") (pintype "passive"))
    )
    (net (code "51") (name "unconnected-(U3-PA6{slash}SPI_MISO-Pad16)") (class "Default")
      (node (ref "U3") (pin "16") (pinfunction "PA6/SPI_MISO_16") (pintype "passive"))
    )
    (net (code "52") (name "unconnected-(U3-PA8{slash}UART_CK-Pad29)") (class "Default")
      (node (ref "U3") (pin "29") (pinfunction "PA8/UART_CK_29") (pintype "passive"))
    )
    (net (code "53") (name "unconnected-(U3-PA9{slash}UART_TX-Pad30)") (class "Default")
      (node (ref "U3") (pin "30") (pinfunction "PA9/UART_TX_30") (pintype "passive"))
    )
    (net (code "54") (name "unconnected-(U3-PA10{slash}UART_RX-Pad31)") (class "Default")
      (node (ref "U3") (pin "31") (pinfunction "PA10/UART_RX_31") (pintype "passive"))
    )
    (net (code "55") (name "unconnected-(U3-PB3-Pad39)") (class "Default")
      (node (ref "U3") (pin "39") (pinfunction "PB3_39") (pintype "passive"))
    )
    (net (code "56") (name "unconnected-(U3-PB8-Pad45)") (class "Default")
      (node (ref "U3") (pin "45") (pinfunction "PB8_45") (pintype "passive"))
    )
    (net (code "57") (name "unconnected-(U3-PB12-Pad25)") (class "Default")
      (node (ref "U3") (pin "25") (pinfunction "PB12_25") (pintype "passive"))
    )
    (net (code "58") (name "unconnected-(U3-PB13-Pad26)") (class "Default")
      (node (ref "U3") (pin "26") (pinfunction "PB13_26") (pintype "passive"))
    )
    (net (code "59") (name "unconnected-(U3-PB15-Pad28)") (class "Default")
      (node (ref "U3") (pin "28") (pinfunction "PB15_28") (pintype "passive"))
    )
    (net (code "60") (name "unconnected-(U3-PC13-Pad2)") (class "Default")
      (node (ref "U3") (pin "2") (pinfunction "PC13_2") (pintype "passive"))
    )
    (net (code "61") (name "unconnected-(U3-VBAT-Pad1)") (class "Default")
      (node (ref "U3") (pin "1") (pinfunction "VBAT_1") (pintype "passive"))
    )
    (net (code "62") (name "unconnected-(U4-CLK-Pad20)") (class "Default")
      (node (ref "U4") (pin "20") (pinfunction "CLK_20") (pintype "passive"))
    )
    (net (code "63") (name "unconnected-(U4-CMD-Pad19)") (class "Default")
      (node (ref "U4") (pin "19") (pinfunction "CMD_19") (pintype "passive"))
    )
    (net (code "64") (name "unconnected-(U4-IO0-Pad25)") (class "Default")
      (node (ref "U4") (pin "25") (pinfunction "IO0_25") (pintype "passive"))
    )
    (net (code "65") (name "unconnected-(U4-IO2-Pad24)") (class "Default")
      (node (ref "U4") (pin "24") (pinfunction "IO2_24") (pintype "passive"))
    )
    (net (code "66") (name "unconnected-(U4-IO4-Pad26)") (class "Default")
      (node (ref "U4") (pin "26") (pinfunction "IO4_26") (pintype "passive"))
    )
    (net (code "67") (name "unconnected-(U4-IO5-Pad29)") (class "Default")
      (node (ref "U4") (pin "29") (pinfunction "IO5_29") (pintype "passive"))
    )
    (net (code "68") (name "unconnected-(U4-IO12-Pad14)") (class "Default")
      (node (ref "U4") (pin "14") (pinfunction "IO12_14") (pintype "passive"))
    )
    (net (code "69") (name "unconnected-(U4-IO13-Pad16)") (class "Default")
      (node (ref "U4") (pin "16") (pinfunction "IO13_16") (pintype "passive"))
    )
    (net (code "70") (name "unconnected-(U4-IO14-Pad13)") (class "Default")
      (node (ref "U4") (pin "13") (pinfunction "IO14_13") (pintype "passive"))
    )
    (net (code "71") (name "unconnected-(U4-IO15-Pad23)") (class "Default")
      (node (ref "U4") (pin "23") (pinfunction "IO15_23") (pintype "passive"))
    )
    (net (code "72") (name "unconnected-(U4-IO16-Pad27)") (class "Default")
      (node (ref "U4") (pin "27") (pinfunction "IO16_27") (pintype "passive"))
    )
    (net (code "73") (name "unconnected-(U4-IO17-Pad28)") (class "Default")
      (node (ref "U4") (pin "28") (pinfunction "IO17_28") (pintype "passive"))
    )
    (net (code "74") (name "unconnected-(U4-IO18-Pad30)") (class "Default")
      (node (ref "U4") (pin "30") (pinfunction "IO18_30") (pintype "passive"))
    )
    (net (code "75") (name "unconnected-(U4-IO19-Pad31)") (class "Default")
      (node (ref "U4") (pin "31") (pinfunction "IO19_31") (pintype "passive"))
    )
    (net (code "76") (name "unconnected-(U4-IO21-Pad33)") (class "Default")
      (node (ref "U4") (pin "33") (pinfunction "IO21_33") (pintype "passive"))
    )
    (net (code "77") (name "unconnected-(U4-IO22-Pad36)") (class "Default")
      (node (ref "U4") (pin "36") (pinfunction "IO22_36") (pintype "passive"))
    )
    (net (code "78") (name "unconnected-(U4-IO23-Pad37)") (class "Default")
      (node (ref "U4") (pin "37") (pinfunction "IO23_37") (pintype "passive"))
    )
    (net (code "79") (name "unconnected-(U4-IO25-Pad10)") (class "Default")
      (node (ref "U4") (pin "10") (pinfunction "IO25_10") (pintype "passive"))
    )
    (net (code "80") (name "unconnected-(U4-IO26-Pad11)") (class "Default")
      (node (ref "U4") (pin "11") (pinfunction "IO26_11") (pintype "passive"))
    )
    (net (code "81") (name "unconnected-(U4-IO27-Pad12)") (class "Default")
      (node (ref "U4") (pin "12") (pinfunction "IO27_12") (pintype "passive"))
    )
    (net (code "82") (name "unconnected-(U4-IO32-Pad8)") (class "Default")
      (node (ref "U4") (pin "8") (pinfunction "IO32_8") (pintype "passive"))
    )
    (net (code "83") (name "unconnected-(U4-IO33-Pad9)") (class "Default")
      (node (ref "U4") (pin "9") (pinfunction "IO33_9") (pintype "passive"))
    )
    (net (code "84") (name "unconnected-(U4-IO34-Pad6)") (class "Default")
      (node (ref "U4") (pin "6") (pinfunction "IO34_6") (pintype "passive"))
    )
    (net (code "85") (name "unconnected-(U4-IO35-Pad7)") (class "Default")
      (node (ref "U4") (pin "7") (pinfunction "IO35_7") (pintype "passive"))
    )
    (net (code "86") (name "unconnected-(U4-NC-Pad32)") (class "Default")
      (node (ref "U4") (pin "32") (pinfunction "NC_32") (pintype "passive"))
    )
    (net (code "87") (name "unconnected-(U4-SD0-Pad21)") (class "Default")
      (node (ref "U4") (pin "21") (pinfunction "SD0_21") (pintype "passive"))
    )
    (net (code "88") (name "unconnected-(U4-SD1-Pad22)") (class "Default")
      (node (ref "U4") (pin "22") (pinfunction "SD1_22") (pintype "passive"))
    )
    (net (code "89") (name "unconnected-(U4-SD2-Pad17)") (class "Default")
      (node (ref "U4") (pin "17") (pinfunction "SD2_17") (pintype "passive"))
    )
    (net (code "90") (name "unconnected-(U4-SD3-Pad18)") (class "Default")
      (node (ref "U4") (pin "18") (pinfunction "SD3_18") (pintype "passive"))
    )
    (net (code "91") (name "unconnected-(U4-SENSOR_VN-Pad5)") (class "Default")
      (node (ref "U4") (pin "5") (pinfunction "SENSOR_VN_5") (pintype "passive"))
    )
    (net (code "92") (name "unconnected-(U4-SENSOR_VP-Pad4)") (class "Default")
      (node (ref "U4") (pin "4") (pinfunction "SENSOR_VP_4") (pintype "passive"))
    )
    (net (code "93") (name "unconnected-(U6-FT{slash}OUT-Pad7)") (class "Default")
      (node (ref "U6") (pin "7") (pinfunction "FT/OUT_7") (pintype "passive"))
    )
    (net (code "94") (name "unconnected-(U7-NC-Pad7)") (class "Default")
      (node (ref "U7") (pin "7") (pinfunction "NC_7") (pintype "passive"))
    )
    (net (code "95") (name "unconnected-(U7-~{ALERT}-Pad6)") (class "Default")
      (node (ref "U7") (pin "6") (pinfunction "~{ALERT}_6") (pintype "passive"))
    )
  )
)
